# Arduino_MEGA2560_ref.net
KiCad netlist of a schematic drawn in EAGLE
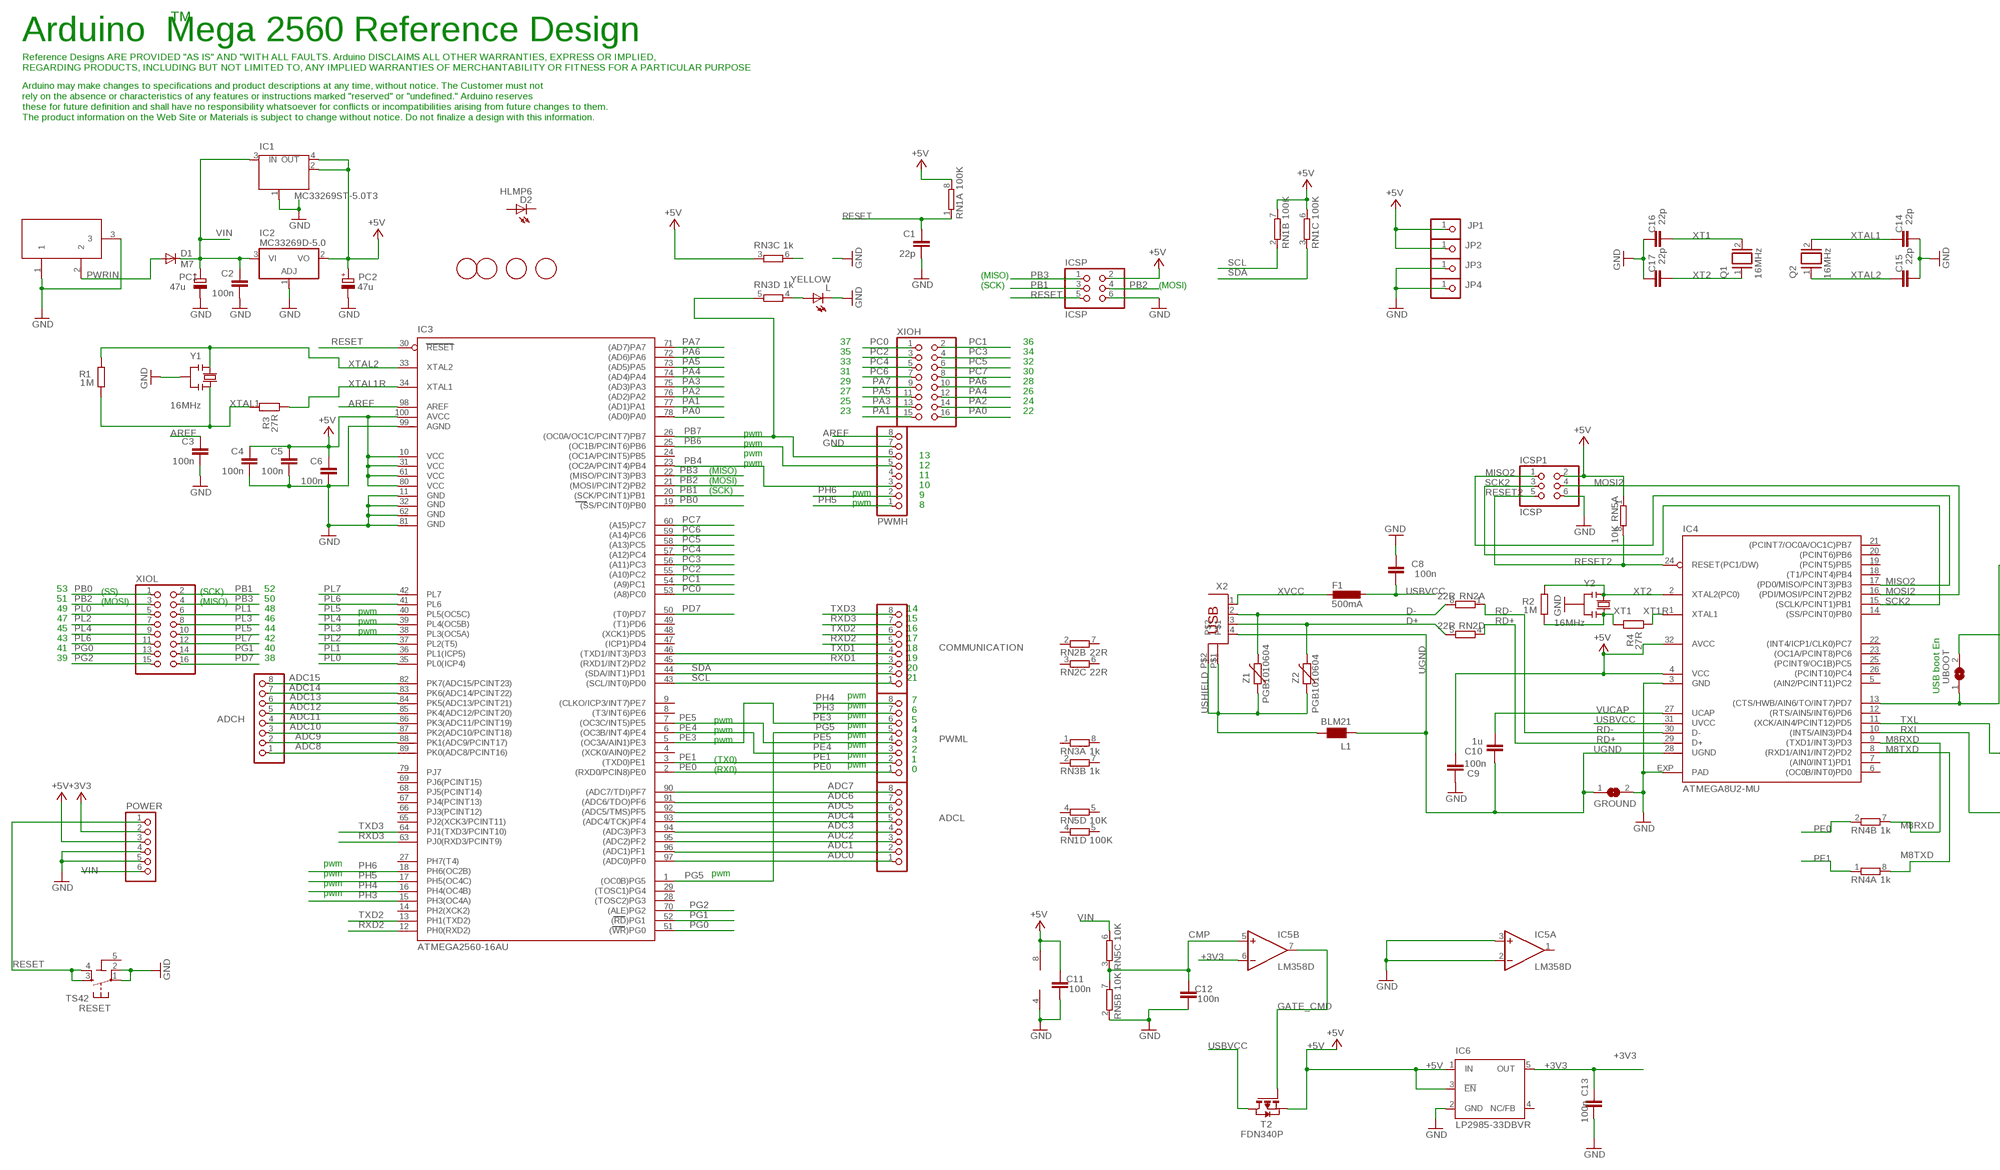
[diagram p0: schematic, sheet 1, part 1 of 2]
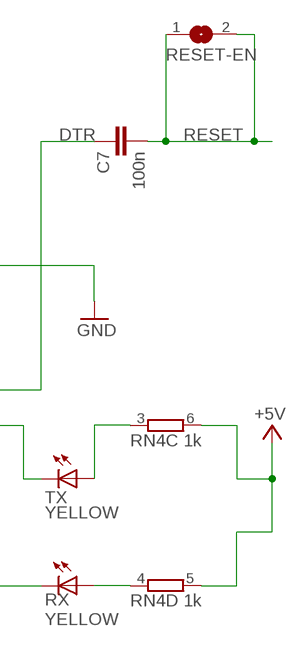
[diagram p1: schematic, sheet 1, part 2 of 2]

(export (version "E")
  (design (tool "Eeschema 10.0.6"))
  (components
    (comp (ref "ADCH")
      (value "PINHD-1X8")
      (footprint "eagle-import:1X08")
      (libsource (lib "eagle-import") (part "PINHD-1X8"))
    )
    (comp (ref "ADCL")
      (value "PINHD-1X8")
      (footprint "eagle-import:1X08")
      (libsource (lib "eagle-import") (part "PINHD-1X8"))
    )
    (comp (ref "C1")
      (value "22p")
      (footprint "eagle-import:C0603-ROUND")
      (libsource (lib "eagle-import") (part "C-EU0603-RND"))
    )
    (comp (ref "C2")
      (value "100n")
      (footprint "eagle-import:C0603-ROUND")
      (libsource (lib "eagle-import") (part "C-EU0603-RND"))
    )
    (comp (ref "C3")
      (value "100n")
      (footprint "eagle-import:C0603-ROUND")
      (libsource (lib "eagle-import") (part "C-EU0603-RND"))
    )
    (comp (ref "C4")
      (value "100n")
      (footprint "eagle-import:C0603-ROUND")
      (libsource (lib "eagle-import") (part "C-EU0603-RND"))
    )
    (comp (ref "C5")
      (value "100n")
      (footprint "eagle-import:C0603-ROUND")
      (libsource (lib "eagle-import") (part "C-EU0603-RND"))
    )
    (comp (ref "C6")
      (value "100n")
      (footprint "eagle-import:C0603-ROUND")
      (libsource (lib "eagle-import") (part "C-EU0603-RND"))
    )
    (comp (ref "C7")
      (value "100n")
      (footprint "eagle-import:C0603-ROUND")
      (libsource (lib "eagle-import") (part "C-EU0603-RND"))
    )
    (comp (ref "C8")
      (value "100n")
      (footprint "eagle-import:C0603")
      (libsource (lib "eagle-import") (part "rcl_C-EUC0603"))
    )
    (comp (ref "C9")
      (value "100n")
      (footprint "eagle-import:C0603-ROUND")
      (libsource (lib "eagle-import") (part "C-EU0603-RND"))
    )
    (comp (ref "C10")
      (value "1u")
      (footprint "eagle-import:C0603-ROUND")
      (libsource (lib "eagle-import") (part "C-EU0603-RND"))
    )
    (comp (ref "C11")
      (value "100n")
      (footprint "eagle-import:C0603")
      (libsource (lib "eagle-import") (part "rcl_C-EUC0603"))
    )
    (comp (ref "C12")
      (value "100n")
      (footprint "eagle-import:C0603-ROUND")
      (libsource (lib "eagle-import") (part "C-EU0603-RND"))
    )
    (comp (ref "C13")
      (value "100n")
      (footprint "eagle-import:C0603-ROUND")
      (libsource (lib "eagle-import") (part "C-EU0603-RND"))
    )
    (comp (ref "C14")
      (value "22p")
      (footprint "eagle-import:C0603-ROUND")
      (libsource (lib "eagle-import") (part "C-EU0603-RND"))
    )
    (comp (ref "C15")
      (value "22p")
      (footprint "eagle-import:C0603-ROUND")
      (libsource (lib "eagle-import") (part "C-EU0603-RND"))
    )
    (comp (ref "C16")
      (value "22p")
      (footprint "eagle-import:C0603-ROUND")
      (libsource (lib "eagle-import") (part "C-EU0603-RND"))
    )
    (comp (ref "C17")
      (value "22p")
      (footprint "eagle-import:C0603-ROUND")
      (libsource (lib "eagle-import") (part "C-EU0603-RND"))
    )
    (comp (ref "COMMUNICATION")
      (value "PINHD-1X8")
      (footprint "eagle-import:1X08")
      (libsource (lib "eagle-import") (part "PINHD-1X8"))
    )
    (comp (ref "D1")
      (value "M7")
      (footprint "eagle-import:SMB")
      (libsource (lib "eagle-import") (part "DIODE-SMB"))
    )
    (comp (ref "D2")
      (value "HLMP6")
      (footprint "eagle-import:HLMP6")
      (fields (field (name "MF") "AGILENT TECHNOLOGIES") (field (name "MPN") "HLMP-6500"))
      (libsource (lib "eagle-import") (part "HLMP6"))
    )
    (comp (ref "F1")
      (value "500mA")
      (footprint "eagle-import:L1812")
      (libsource (lib "eagle-import") (part "L-EUL1812"))
    )
    (comp (ref "GROUND")
      (value "SJ")
      (footprint "eagle-import:SJ")
      (libsource (lib "eagle-import") (part "SJ"))
    )
    (comp (ref "IC1")
      (value "MC33269ST-5.0T3")
      (footprint "eagle-import:SOT223")
      (libsource (lib "eagle-import") (part "MC33269ST-3.3T3"))
    )
    (comp (ref "IC2")
      (value "MC33269D-5.0")
      (footprint "eagle-import:DPACK")
      (libsource (lib "eagle-import") (part "MC33269?D-5.0"))
    )
    (comp (ref "IC3")
      (value "ATMEGA2560-16AU")
      (footprint "eagle-import:TQFP100")
      (libsource (lib "eagle-import") (part "ATMEGAAU1280-16"))
    )
    (comp (ref "IC4")
      (value "ATMEGA8U2-MU")
      (footprint "eagle-import:QFN32")
      (libsource (lib "eagle-import") (part "ATMEGA8U2-MU"))
    )
    (comp (ref "IC5")
      (value "LM358D")
      (footprint "eagle-import:SO08")
      (libsource (lib "eagle-import") (part "LM358D"))
    )
    (comp (ref "IC6")
      (value "LP2985-33DBVR")
      (footprint "eagle-import:SOT23-DBV")
      (libsource (lib "eagle-import") (part "TPS77033"))
    )
    (comp (ref "ICSP")
      (value "ICSP")
      (footprint "eagle-import:2X03")
      (libsource (lib "eagle-import") (part "PINHD-2X3"))
    )
    (comp (ref "ICSP1")
      (value "ICSP")
      (footprint "eagle-import:2X03")
      (libsource (lib "eagle-import") (part "PINHD-2X3"))
    )
    (comp (ref "JP1")
      (value "PINHD-1X1")
      (footprint "eagle-import:1X01")
      (libsource (lib "eagle-import") (part "PINHD-1X1"))
    )
    (comp (ref "JP2")
      (value "PINHD-1X1")
      (footprint "eagle-import:1X01")
      (libsource (lib "eagle-import") (part "PINHD-1X1"))
    )
    (comp (ref "JP3")
      (value "PINHD-1X1")
      (footprint "eagle-import:1X01")
      (libsource (lib "eagle-import") (part "PINHD-1X1"))
    )
    (comp (ref "JP4")
      (value "PINHD-1X1")
      (footprint "eagle-import:1X01")
      (libsource (lib "eagle-import") (part "PINHD-1X1"))
    )
    (comp (ref "L")
      (value "YELLOW")
      (footprint "eagle-import:CHIP-LED0805")
      (libsource (lib "eagle-import") (part "LEDCHIP-LED0805"))
    )
    (comp (ref "L1")
      (value "BLM21")
      (footprint "eagle-import:0805")
      (libsource (lib "eagle-import") (part "WE-CBF_0805"))
    )
    (comp (ref "PC1")
      (value "47u")
      (footprint "eagle-import:PANASONIC_D")
      (libsource (lib "eagle-import") (part "CPOL-EUD"))
    )
    (comp (ref "PC2")
      (value "47u")
      (footprint "eagle-import:PANASONIC_D")
      (libsource (lib "eagle-import") (part "CPOL-EUD"))
    )
    (comp (ref "POWER")
      (value "PINHD-1X6")
      (footprint "eagle-import:1X06")
      (libsource (lib "eagle-import") (part "PINHD-1X6"))
    )
    (comp (ref "PWMH")
      (value "PINHD-1X8")
      (footprint "eagle-import:1X08")
      (libsource (lib "eagle-import") (part "PINHD-1X8"))
    )
    (comp (ref "PWML")
      (value "PINHD-1X8")
      (footprint "eagle-import:1X08")
      (libsource (lib "eagle-import") (part "PINHD-1X8"))
    )
    (comp (ref "Q1")
      (value "16MHz")
      (footprint "eagle-import:QS")
      (libsource (lib "eagle-import") (part "XTAL/S"))
    )
    (comp (ref "Q2")
      (value "16MHz")
      (footprint "eagle-import:QS")
      (libsource (lib "eagle-import") (part "XTAL/S"))
    )
    (comp (ref "R1")
      (value "1M")
      (footprint "eagle-import:R0603-ROUND")
      (libsource (lib "eagle-import") (part "R-EU_R0603"))
    )
    (comp (ref "R2")
      (value "1M")
      (footprint "eagle-import:R0603-ROUND")
      (libsource (lib "eagle-import") (part "R-EU_R0603"))
    )
    (comp (ref "R3")
      (value "27R")
      (footprint "eagle-import:R0603-ROUND")
      (libsource (lib "eagle-import") (part "R-EU_R0603"))
    )
    (comp (ref "R4")
      (value "27R")
      (footprint "eagle-import:R0603-ROUND")
      (libsource (lib "eagle-import") (part "R-EU_R0603"))
    )
    (comp (ref "RESET")
      (value "TS42")
      (footprint "eagle-import:TS42")
      (libsource (lib "eagle-import") (part "TS42"))
    )
    (comp (ref "RESET-EN")
      (value "SJ")
      (footprint "eagle-import:SJ")
      (libsource (lib "eagle-import") (part "SJ"))
    )
    (comp (ref "RN1")
      (value "100K")
      (footprint "eagle-import:CAT16")
      (libsource (lib "eagle-import") (part "4R-NCAT16"))
    )
    (comp (ref "RN2")
      (value "22R")
      (footprint "eagle-import:CAY16")
      (libsource (lib "eagle-import") (part "4R-NCAY16"))
    )
    (comp (ref "RN3")
      (value "1k")
      (footprint "eagle-import:CAY16")
      (libsource (lib "eagle-import") (part "4R-NCAY16"))
    )
    (comp (ref "RN4")
      (value "1k")
      (footprint "eagle-import:CAY16")
      (libsource (lib "eagle-import") (part "4R-NCAY16"))
    )
    (comp (ref "RN5")
      (value "10K")
      (footprint "eagle-import:CAT16")
      (libsource (lib "eagle-import") (part "4R-NCAT16"))
    )
    (comp (ref "RX")
      (value "YELLOW")
      (footprint "eagle-import:CHIP-LED0805")
      (libsource (lib "eagle-import") (part "LEDCHIP-LED0805"))
    )
    (comp (ref "T2")
      (value "FDN340P")
      (footprint "eagle-import:SOT-23")
      (libsource (lib "eagle-import") (part "PMOSSOT23"))
    )
    (comp (ref "TX")
      (value "YELLOW")
      (footprint "eagle-import:CHIP-LED0805")
      (libsource (lib "eagle-import") (part "LEDCHIP-LED0805"))
    )
    (comp (ref "U$2")
      (value "FIDUCIALMOUNT")
      (footprint "eagle-import:FIDUCIA-MOUNT")
      (libsource (lib "eagle-import") (part "FIDUCIALMOUNT"))
    )
    (comp (ref "U$3")
      (value "FIDUCIALMOUNT")
      (footprint "eagle-import:FIDUCIA-MOUNT")
      (libsource (lib "eagle-import") (part "FIDUCIALMOUNT"))
    )
    (comp (ref "U$4")
      (value "FIDUCIALMOUNT")
      (footprint "eagle-import:FIDUCIA-MOUNT")
      (libsource (lib "eagle-import") (part "FIDUCIALMOUNT"))
    )
    (comp (ref "U$5")
      (value "FIDUCIALMOUNT")
      (footprint "eagle-import:FIDUCIA-MOUNT")
      (libsource (lib "eagle-import") (part "FIDUCIALMOUNT"))
    )
    (comp (ref "UBOOT")
      (value "SJ")
      (footprint "eagle-import:SJ")
      (libsource (lib "eagle-import") (part "SJ"))
    )
    (comp (ref "X1")
      (value "DC21MMX")
      (footprint "eagle-import:DC-21MM")
      (libsource (lib "eagle-import") (part "DC21MMX"))
    )
    (comp (ref "X2")
      (value "PN61729")
      (footprint "eagle-import:PN61729")
      (libsource (lib "eagle-import") (part "PN61729"))
    )
    (comp (ref "XIOH")
      (value "PINHD-2X8")
      (footprint "eagle-import:2X08")
      (libsource (lib "eagle-import") (part "PINHD-2X8"))
    )
    (comp (ref "XIOL")
      (value "PINHD-2X8")
      (footprint "eagle-import:2X08")
      (libsource (lib "eagle-import") (part "PINHD-2X8"))
    )
    (comp (ref "Y1")
      (value "16MHz")
      (footprint "eagle-import:RESONATOR")
      (libsource (lib "eagle-import") (part "RESONATORMU"))
    )
    (comp (ref "Y2")
      (value "16MHz")
      (footprint "eagle-import:RESONATOR")
      (libsource (lib "eagle-import") (part "RESONATORMU"))
    )
    (comp (ref "Z1")
      (value "PGB1010604")
      (footprint "eagle-import:CT_CN0603")
      (libsource (lib "eagle-import") (part "VARISTORCN0603"))
    )
    (comp (ref "Z2")
      (value "PGB1010604")
      (footprint "eagle-import:CT_CN0603")
      (libsource (lib "eagle-import") (part "VARISTORCN0603"))
    )
  )
  (nets
    (net (code "1") (name "+3V3") (class "Default")
      (node (ref "C13") (pin "2") (pinfunction "2_2") (pintype "passive"))
      (node (ref "IC5") (pin "6") (pinfunction "-IN_6") (pintype "input"))
      (node (ref "IC6") (pin "5") (pinfunction "OUT_5") (pintype "passive"))
      (node (ref "POWER") (pin "2") (pinfunction "2_2") (pintype "passive"))
    )
    (net (code "2") (name "+5V") (class "Default")
      (node (ref "C11") (pin "2") (pinfunction "2_2") (pintype "passive"))
      (node (ref "C4") (pin "1") (pinfunction "1_1") (pintype "passive"))
      (node (ref "C5") (pin "1") (pinfunction "1_1") (pintype "passive"))
      (node (ref "C6") (pin "1") (pinfunction "1_1") (pintype "passive"))
      (node (ref "C9") (pin "1") (pinfunction "1_1") (pintype "passive"))
      (node (ref "IC1") (pin "2") (pinfunction "OUT_2") (pintype "passive"))
      (node (ref "IC1") (pin "4") (pinfunction "OUT_4") (pintype "passive"))
      (node (ref "IC2") (pin "2") (pinfunction "VO_2") (pintype "passive"))
      (node (ref "IC3") (pin "10") (pinfunction "VCC_10") (pintype "power_in"))
      (node (ref "IC3") (pin "100") (pinfunction "AVCC_100") (pintype "power_in"))
      (node (ref "IC3") (pin "31") (pinfunction "VCC1_31") (pintype "power_in"))
      (node (ref "IC3") (pin "61") (pinfunction "VCC2_61") (pintype "power_in"))
      (node (ref "IC3") (pin "80") (pinfunction "VCC3_80") (pintype "power_in"))
      (node (ref "IC4") (pin "32") (pinfunction "AVCC_32") (pintype "power_in"))
      (node (ref "IC4") (pin "4") (pinfunction "VCC_4") (pintype "power_in"))
      (node (ref "IC5") (pin "8") (pinfunction "V+_8") (pintype "power_in"))
      (node (ref "IC6") (pin "1") (pinfunction "IN_1") (pintype "input"))
      (node (ref "IC6") (pin "3") (pinfunction "~{EN}_3") (pintype "input"))
      (node (ref "ICSP") (pin "2") (pinfunction "2_2") (pintype "passive"))
      (node (ref "ICSP1") (pin "2") (pinfunction "2_2") (pintype "passive"))
      (node (ref "JP1") (pin "1") (pinfunction "1_1") (pintype "passive"))
      (node (ref "JP2") (pin "1") (pinfunction "1_1") (pintype "passive"))
      (node (ref "PC2") (pin "+") (pinfunction "+_+") (pintype "passive"))
      (node (ref "POWER") (pin "3") (pinfunction "3_3") (pintype "passive"))
      (node (ref "RN1") (pin "6") (pinfunction "2_6") (pintype "passive"))
      (node (ref "RN1") (pin "7") (pinfunction "2_7") (pintype "passive"))
      (node (ref "RN1") (pin "8") (pinfunction "2_8") (pintype "passive"))
      (node (ref "RN3") (pin "3") (pinfunction "1_3") (pintype "passive"))
      (node (ref "RN4") (pin "5") (pinfunction "2_5") (pintype "passive"))
      (node (ref "RN4") (pin "6") (pinfunction "2_6") (pintype "passive"))
      (node (ref "RN5") (pin "1") (pinfunction "1_1") (pintype "passive"))
      (node (ref "T2") (pin "2") (pinfunction "S_2") (pintype "passive"))
    )
    (net (code "3") (name "/5-GND") (class "Default")
      (node (ref "RESET") (pin "5") (pinfunction "5-GND_5") (pintype "power_in"))
    )
    (net (code "4") (name "/ADC0") (class "Default")
      (node (ref "ADCL") (pin "1") (pinfunction "1_1") (pintype "passive"))
      (node (ref "IC3") (pin "97") (pinfunction "(ADC0)PF0_97") (pintype "bidirectional"))
    )
    (net (code "5") (name "/ADC1") (class "Default")
      (node (ref "ADCL") (pin "2") (pinfunction "2_2") (pintype "passive"))
      (node (ref "IC3") (pin "96") (pinfunction "(ADC1)PF1_96") (pintype "bidirectional"))
    )
    (net (code "6") (name "/ADC2") (class "Default")
      (node (ref "ADCL") (pin "3") (pinfunction "3_3") (pintype "passive"))
      (node (ref "IC3") (pin "95") (pinfunction "(ADC2)PF2_95") (pintype "bidirectional"))
    )
    (net (code "7") (name "/ADC3") (class "Default")
      (node (ref "ADCL") (pin "4") (pinfunction "4_4") (pintype "passive"))
      (node (ref "IC3") (pin "94") (pinfunction "(ADC3)PF3_94") (pintype "bidirectional"))
    )
    (net (code "8") (name "/ADC4") (class "Default")
      (node (ref "ADCL") (pin "5") (pinfunction "5_5") (pintype "passive"))
      (node (ref "IC3") (pin "93") (pinfunction "(ADC4/TCK)PF4_93") (pintype "bidirectional"))
    )
    (net (code "9") (name "/ADC5") (class "Default")
      (node (ref "ADCL") (pin "6") (pinfunction "6_6") (pintype "passive"))
      (node (ref "IC3") (pin "92") (pinfunction "(ADC5/TMS)PF5_92") (pintype "bidirectional"))
    )
    (net (code "10") (name "/ADC6") (class "Default")
      (node (ref "ADCL") (pin "7") (pinfunction "7_7") (pintype "passive"))
      (node (ref "IC3") (pin "91") (pinfunction "(ADC6/TDO)PF6_91") (pintype "bidirectional"))
    )
    (net (code "11") (name "/ADC7") (class "Default")
      (node (ref "ADCL") (pin "8") (pinfunction "8_8") (pintype "passive"))
      (node (ref "IC3") (pin "90") (pinfunction "(ADC7/TDI)PF7_90") (pintype "bidirectional"))
    )
    (net (code "12") (name "/ADC8") (class "Default")
      (node (ref "ADCH") (pin "1") (pinfunction "1_1") (pintype "passive"))
      (node (ref "IC3") (pin "89") (pinfunction "PK0(ADC8/PCINT16)_89") (pintype "bidirectional"))
    )
    (net (code "13") (name "/ADC9") (class "Default")
      (node (ref "ADCH") (pin "2") (pinfunction "2_2") (pintype "passive"))
      (node (ref "IC3") (pin "88") (pinfunction "PK1(ADC9/PCINT17)_88") (pintype "bidirectional"))
    )
    (net (code "14") (name "/ADC10") (class "Default")
      (node (ref "ADCH") (pin "3") (pinfunction "3_3") (pintype "passive"))
      (node (ref "IC3") (pin "87") (pinfunction "PK2(ADC10/PCINT18)_87") (pintype "bidirectional"))
    )
    (net (code "15") (name "/ADC11") (class "Default")
      (node (ref "ADCH") (pin "4") (pinfunction "4_4") (pintype "passive"))
      (node (ref "IC3") (pin "86") (pinfunction "PK3(ADC11/PCINT19)_86") (pintype "bidirectional"))
    )
    (net (code "16") (name "/ADC12") (class "Default")
      (node (ref "ADCH") (pin "5") (pinfunction "5_5") (pintype "passive"))
      (node (ref "IC3") (pin "85") (pinfunction "PK4(ADC12/PCINT20)_85") (pintype "bidirectional"))
    )
    (net (code "17") (name "/ADC13") (class "Default")
      (node (ref "ADCH") (pin "6") (pinfunction "6_6") (pintype "passive"))
      (node (ref "IC3") (pin "84") (pinfunction "PK5(ADC13/PCINT21)_84") (pintype "bidirectional"))
    )
    (net (code "18") (name "/ADC14") (class "Default")
      (node (ref "ADCH") (pin "7") (pinfunction "7_7") (pintype "passive"))
      (node (ref "IC3") (pin "83") (pinfunction "PK6(ADC14/PCINT22)_83") (pintype "bidirectional"))
    )
    (net (code "19") (name "/ADC15") (class "Default")
      (node (ref "ADCH") (pin "8") (pinfunction "8_8") (pintype "passive"))
      (node (ref "IC3") (pin "82") (pinfunction "PK7(ADC15/PCINT23)_82") (pintype "bidirectional"))
    )
    (net (code "20") (name "/AREF") (class "Default")
      (node (ref "C3") (pin "1") (pinfunction "1_1") (pintype "passive"))
      (node (ref "IC3") (pin "98") (pinfunction "AREF_98") (pintype "bidirectional"))
      (node (ref "PWMH") (pin "8") (pinfunction "8_8") (pintype "passive"))
    )
    (net (code "21") (name "/CMP") (class "Default")
      (node (ref "C12") (pin "2") (pinfunction "2_2") (pintype "passive"))
      (node (ref "IC5") (pin "5") (pinfunction "+IN_5") (pintype "input"))
      (node (ref "RN5") (pin "3") (pinfunction "1_3") (pintype "passive"))
      (node (ref "RN5") (pin "7") (pinfunction "2_7") (pintype "passive"))
    )
    (net (code "22") (name "/D+") (class "Default")
      (node (ref "RN2") (pin "5") (pinfunction "2_5") (pintype "passive"))
      (node (ref "X2") (pin "3") (pinfunction "3_3") (pintype "bidirectional"))
      (node (ref "Z2") (pin "2") (pinfunction "2_2") (pintype "passive"))
    )
    (net (code "23") (name "/D-") (class "Default")
      (node (ref "RN2") (pin "8") (pinfunction "2_8") (pintype "passive"))
      (node (ref "X2") (pin "2") (pinfunction "2_2") (pintype "bidirectional"))
      (node (ref "Z1") (pin "2") (pinfunction "2_2") (pintype "passive"))
    )
    (net (code "24") (name "/DTR") (class "Default")
      (node (ref "C7") (pin "1") (pinfunction "1_1") (pintype "passive"))
      (node (ref "IC4") (pin "13") (pinfunction "(CTS/HWB/AIN6/TO/INT7)PD7_13") (pintype "bidirectional"))
      (node (ref "UBOOT") (pin "1") (pinfunction "1_1") (pintype "passive"))
    )
    (net (code "25") (name "/GATE_CMD") (class "Default")
      (node (ref "IC5") (pin "7") (pinfunction "OUT_7") (pintype "output"))
      (node (ref "T2") (pin "3") (pinfunction "G_3") (pintype "passive"))
    )
    (net (code "26") (name "/M8RXD") (class "Default")
      (node (ref "IC4") (pin "9") (pinfunction "(TXD1/INT3)PD3_9") (pintype "bidirectional"))
      (node (ref "RN4") (pin "7") (pinfunction "2_7") (pintype "passive"))
    )
    (net (code "27") (name "/M8TXD") (class "Default")
      (node (ref "IC4") (pin "8") (pinfunction "(RXD1/AIN1/INT2)PD2_8") (pintype "bidirectional"))
      (node (ref "RN4") (pin "8") (pinfunction "2_8") (pintype "passive"))
    )
    (net (code "28") (name "/MISO2") (class "Default")
      (node (ref "IC4") (pin "17") (pinfunction "(PD0/MISO/PCINT3)PB3_17") (pintype "bidirectional"))
      (node (ref "ICSP1") (pin "1") (pinfunction "1_1") (pintype "passive"))
    )
    (net (code "29") (name "/MOSI2") (class "Default")
      (node (ref "IC4") (pin "16") (pinfunction "(PDI/MOSI/PCINT2)PB2_16") (pintype "bidirectional"))
      (node (ref "ICSP1") (pin "4") (pinfunction "4_4") (pintype "passive"))
    )
    (net (code "30") (name "/PA0") (class "Default")
      (node (ref "IC3") (pin "78") (pinfunction "(AD0)PA0_78") (pintype "bidirectional"))
      (node (ref "XIOH") (pin "16") (pinfunction "16_16") (pintype "passive"))
    )
    (net (code "31") (name "/PA1") (class "Default")
      (node (ref "IC3") (pin "77") (pinfunction "(AD1)PA1_77") (pintype "bidirectional"))
      (node (ref "XIOH") (pin "15") (pinfunction "15_15") (pintype "passive"))
    )
    (net (code "32") (name "/PA2") (class "Default")
      (node (ref "IC3") (pin "76") (pinfunction "(AD2)PA2_76") (pintype "bidirectional"))
      (node (ref "XIOH") (pin "14") (pinfunction "14_14") (pintype "passive"))
    )
    (net (code "33") (name "/PA3") (class "Default")
      (node (ref "IC3") (pin "75") (pinfunction "(AD3)PA3_75") (pintype "bidirectional"))
      (node (ref "XIOH") (pin "13") (pinfunction "13_13") (pintype "passive"))
    )
    (net (code "34") (name "/PA4") (class "Default")
      (node (ref "IC3") (pin "74") (pinfunction "(AD4)PA4_74") (pintype "bidirectional"))
      (node (ref "XIOH") (pin "12") (pinfunction "12_12") (pintype "passive"))
    )
    (net (code "35") (name "/PA5") (class "Default")
      (node (ref "IC3") (pin "73") (pinfunction "(AD5)PA5_73") (pintype "bidirectional"))
      (node (ref "XIOH") (pin "11") (pinfunction "11_11") (pintype "passive"))
    )
    (net (code "36") (name "/PA6") (class "Default")
      (node (ref "IC3") (pin "72") (pinfunction "(AD6)PA6_72") (pintype "bidirectional"))
      (node (ref "XIOH") (pin "10") (pinfunction "10_10") (pintype "passive"))
    )
    (net (code "37") (name "/PA7") (class "Default")
      (node (ref "IC3") (pin "71") (pinfunction "(AD7)PA7_71") (pintype "bidirectional"))
      (node (ref "XIOH") (pin "9") (pinfunction "9_9") (pintype "passive"))
    )
    (net (code "38") (name "/PB0") (class "Default")
      (node (ref "IC3") (pin "19") (pinfunction "(SS/PCINT0)PB0_19") (pintype "bidirectional"))
      (node (ref "XIOL") (pin "1") (pinfunction "1_1") (pintype "passive"))
    )
    (net (code "39") (name "/PB1") (class "Default")
      (node (ref "IC3") (pin "20") (pinfunction "(SCK/PCINT1)PB1_20") (pintype "bidirectional"))
      (node (ref "ICSP") (pin "3") (pinfunction "3_3") (pintype "passive"))
      (node (ref "XIOL") (pin "2") (pinfunction "2_2") (pintype "passive"))
    )
    (net (code "40") (name "/PB2") (class "Default")
      (node (ref "IC3") (pin "21") (pinfunction "(MOSI/PCINT2)PB2_21") (pintype "bidirectional"))
      (node (ref "ICSP") (pin "4") (pinfunction "4_4") (pintype "passive"))
      (node (ref "XIOL") (pin "3") (pinfunction "3_3") (pintype "passive"))
    )
    (net (code "41") (name "/PB3") (class "Default")
      (node (ref "IC3") (pin "22") (pinfunction "(MISO/PCINT3)PB3_22") (pintype "bidirectional"))
      (node (ref "ICSP") (pin "1") (pinfunction "1_1") (pintype "passive"))
      (node (ref "XIOL") (pin "4") (pinfunction "4_4") (pintype "passive"))
    )
    (net (code "42") (name "/PB4") (class "Default")
      (node (ref "IC3") (pin "23") (pinfunction "(OC2A/PCINT4)PB4_23") (pintype "bidirectional"))
      (node (ref "PWMH") (pin "3") (pinfunction "3_3") (pintype "passive"))
    )
    (net (code "43") (name "/PB6") (class "Default")
      (node (ref "IC3") (pin "25") (pinfunction "(OC1B/PCINT6)PB6_25") (pintype "bidirectional"))
      (node (ref "PWMH") (pin "5") (pinfunction "5_5") (pintype "passive"))
    )
    (net (code "44") (name "/PB7") (class "Default")
      (node (ref "IC3") (pin "26") (pinfunction "(OC0A/OC1C/PCINT7)PB7_26") (pintype "bidirectional"))
      (node (ref "PWMH") (pin "6") (pinfunction "6_6") (pintype "passive"))
      (node (ref "RN3") (pin "5") (pinfunction "2_5") (pintype "passive"))
    )
    (net (code "45") (name "/PC0") (class "Default")
      (node (ref "IC3") (pin "53") (pinfunction "(A8)PC0_53") (pintype "bidirectional"))
      (node (ref "XIOH") (pin "1") (pinfunction "1_1") (pintype "passive"))
    )
    (net (code "46") (name "/PC1") (class "Default")
      (node (ref "IC3") (pin "54") (pinfunction "(A9)PC1_54") (pintype "bidirectional"))
      (node (ref "XIOH") (pin "2") (pinfunction "2_2") (pintype "passive"))
    )
    (net (code "47") (name "/PC2") (class "Default")
      (node (ref "IC3") (pin "55") (pinfunction "(A10)PC2_55") (pintype "bidirectional"))
      (node (ref "XIOH") (pin "3") (pinfunction "3_3") (pintype "passive"))
    )
    (net (code "48") (name "/PC3") (class "Default")
      (node (ref "IC3") (pin "56") (pinfunction "(A11)PC3_56") (pintype "bidirectional"))
      (node (ref "XIOH") (pin "4") (pinfunction "4_4") (pintype "passive"))
    )
    (net (code "49") (name "/PC4") (class "Default")
      (node (ref "IC3") (pin "57") (pinfunction "(A12)PC4_57") (pintype "bidirectional"))
      (node (ref "XIOH") (pin "5") (pinfunction "5_5") (pintype "passive"))
    )
    (net (code "50") (name "/PC5") (class "Default")
      (node (ref "IC3") (pin "58") (pinfunction "(A13)PC5_58") (pintype "bidirectional"))
      (node (ref "XIOH") (pin "6") (pinfunction "6_6") (pintype "passive"))
    )
    (net (code "51") (name "/PC6") (class "Default")
      (node (ref "IC3") (pin "59") (pinfunction "(A14)PC6_59") (pintype "bidirectional"))
      (node (ref "XIOH") (pin "7") (pinfunction "7_7") (pintype "passive"))
    )
    (net (code "52") (name "/PC7") (class "Default")
      (node (ref "IC3") (pin "60") (pinfunction "(A15)PC7_60") (pintype "bidirectional"))
      (node (ref "XIOH") (pin "8") (pinfunction "8_8") (pintype "passive"))
    )
    (net (code "53") (name "/PD7") (class "Default")
      (node (ref "IC3") (pin "50") (pinfunction "(T0)PD7_50") (pintype "bidirectional"))
      (node (ref "XIOL") (pin "16") (pinfunction "16_16") (pintype "passive"))
    )
    (net (code "54") (name "/PE0") (class "Default")
      (node (ref "IC3") (pin "2") (pinfunction "(RXD0/PCIN8)PE0_2") (pintype "bidirectional"))
      (node (ref "PWML") (pin "1") (pinfunction "1_1") (pintype "passive"))
      (node (ref "RN4") (pin "2") (pinfunction "1_2") (pintype "passive"))
    )
    (net (code "55") (name "/PE1") (class "Default")
      (node (ref "IC3") (pin "3") (pinfunction "(TXD0)PE1_3") (pintype "bidirectional"))
      (node (ref "PWML") (pin "2") (pinfunction "2_2") (pintype "passive"))
      (node (ref "RN4") (pin "1") (pinfunction "1_1") (pintype "passive"))
    )
    (net (code "56") (name "/PE3") (class "Default")
      (node (ref "IC3") (pin "5") (pinfunction "(OC3A/AIN1)PE3_5") (pintype "bidirectional"))
      (node (ref "PWML") (pin "6") (pinfunction "6_6") (pintype "passive"))
    )
    (net (code "57") (name "/PE4") (class "Default")
      (node (ref "IC3") (pin "6") (pinfunction "(OC3B/INT4)PE4_6") (pintype "bidirectional"))
      (node (ref "PWML") (pin "3") (pinfunction "3_3") (pintype "passive"))
    )
    (net (code "58") (name "/PE5") (class "Default")
      (node (ref "IC3") (pin "7") (pinfunction "(OC3C/INT5)PE5_7") (pintype "bidirectional"))
      (node (ref "PWML") (pin "4") (pinfunction "4_4") (pintype "passive"))
    )
    (net (code "59") (name "/PG0") (class "Default")
      (node (ref "IC3") (pin "51") (pinfunction "(WR)PG0_51") (pintype "bidirectional"))
      (node (ref "XIOL") (pin "13") (pinfunction "13_13") (pintype "passive"))
    )
    (net (code "60") (name "/PG1") (class "Default")
      (node (ref "IC3") (pin "52") (pinfunction "(RD)PG1_52") (pintype "bidirectional"))
      (node (ref "XIOL") (pin "14") (pinfunction "14_14") (pintype "passive"))
    )
    (net (code "61") (name "/PG2") (class "Default")
      (node (ref "IC3") (pin "70") (pinfunction "(ALE)PG2_70") (pintype "bidirectional"))
      (node (ref "XIOL") (pin "15") (pinfunction "15_15") (pintype "passive"))
    )
    (net (code "62") (name "/PG5") (class "Default")
      (node (ref "IC3") (pin "1") (pinfunction "(OC0B)PG5_1") (pintype "bidirectional"))
      (node (ref "PWML") (pin "5") (pinfunction "5_5") (pintype "passive"))
    )
    (net (code "63") (name "/PH3") (class "Default")
      (node (ref "IC3") (pin "15") (pinfunction "PH3(OC4A)_15") (pintype "bidirectional"))
      (node (ref "PWML") (pin "7") (pinfunction "7_7") (pintype "passive"))
    )
    (net (code "64") (name "/PH4") (class "Default")
      (node (ref "IC3") (pin "16") (pinfunction "PH4(OC4B)_16") (pintype "bidirectional"))
      (node (ref "PWML") (pin "8") (pinfunction "8_8") (pintype "passive"))
    )
    (net (code "65") (name "/PH5") (class "Default")
      (node (ref "IC3") (pin "17") (pinfunction "PH5(OC4C)_17") (pintype "bidirectional"))
      (node (ref "PWMH") (pin "1") (pinfunction "1_1") (pintype "passive"))
    )
    (net (code "66") (name "/PH6") (class "Default")
      (node (ref "IC3") (pin "18") (pinfunction "PH6(OC2B)_18") (pintype "bidirectional"))
      (node (ref "PWMH") (pin "2") (pinfunction "2_2") (pintype "passive"))
    )
    (net (code "67") (name "/PL0") (class "Default")
      (node (ref "IC3") (pin "35") (pinfunction "PL0(ICP4)_35") (pintype "bidirectional"))
      (node (ref "XIOL") (pin "5") (pinfunction "5_5") (pintype "passive"))
    )
    (net (code "68") (name "/PL1") (class "Default")
      (node (ref "IC3") (pin "36") (pinfunction "PL1(ICP5)_36") (pintype "bidirectional"))
      (node (ref "XIOL") (pin "6") (pinfunction "6_6") (pintype "passive"))
    )
    (net (code "69") (name "/PL2") (class "Default")
      (node (ref "IC3") (pin "37") (pinfunction "PL2(T5)_37") (pintype "bidirectional"))
      (node (ref "XIOL") (pin "7") (pinfunction "7_7") (pintype "passive"))
    )
    (net (code "70") (name "/PL3") (class "Default")
      (node (ref "IC3") (pin "38") (pinfunction "PL3(OC5A)_38") (pintype "bidirectional"))
      (node (ref "XIOL") (pin "8") (pinfunction "8_8") (pintype "passive"))
    )
    (net (code "71") (name "/PL4") (class "Default")
      (node (ref "IC3") (pin "39") (pinfunction "PL4(OC5B)_39") (pintype "bidirectional"))
      (node (ref "XIOL") (pin "9") (pinfunction "9_9") (pintype "passive"))
    )
    (net (code "72") (name "/PL5") (class "Default")
      (node (ref "IC3") (pin "40") (pinfunction "PL5(OC5C)_40") (pintype "bidirectional"))
      (node (ref "XIOL") (pin "10") (pinfunction "10_10") (pintype "passive"))
    )
    (net (code "73") (name "/PL6") (class "Default")
      (node (ref "IC3") (pin "41") (pinfunction "PL6_41") (pintype "bidirectional"))
      (node (ref "XIOL") (pin "11") (pinfunction "11_11") (pintype "passive"))
    )
    (net (code "74") (name "/PL7") (class "Default")
      (node (ref "IC3") (pin "42") (pinfunction "PL7_42") (pintype "bidirectional"))
      (node (ref "XIOL") (pin "12") (pinfunction "12_12") (pintype "passive"))
    )
    (net (code "75") (name "/PWRIN") (class "Default")
      (node (ref "D1") (pin "A") (pinfunction "A_A") (pintype "passive"))
      (node (ref "X1") (pin "2") (pinfunction "2_2") (pintype "power_in"))
    )
    (net (code "76") (name "/RD+") (class "Default")
      (node (ref "IC4") (pin "29") (pinfunction "D+_29") (pintype "bidirectional"))
      (node (ref "RN2") (pin "4") (pinfunction "1_4") (pintype "passive"))
    )
    (net (code "77") (name "/RD-") (class "Default")
      (node (ref "IC4") (pin "30") (pinfunction "D-_30") (pintype "bidirectional"))
      (node (ref "RN2") (pin "1") (pinfunction "1_1") (pintype "passive"))
    )
    (net (code "78") (name "/RESET") (class "Default")
      (node (ref "C1") (pin "1") (pinfunction "1_1") (pintype "passive"))
      (node (ref "C7") (pin "2") (pinfunction "2_2") (pintype "passive"))
      (node (ref "IC3") (pin "30") (pinfunction "RESET_30") (pintype "input"))
      (node (ref "ICSP") (pin "5") (pinfunction "5_5") (pintype "passive"))
      (node (ref "POWER") (pin "1") (pinfunction "1_1") (pintype "passive"))
      (node (ref "RESET") (pin "3") (pinfunction "3_3") (pintype "passive"))
      (node (ref "RESET") (pin "4") (pinfunction "4_4") (pintype "passive"))
      (node (ref "RESET-EN") (pin "1") (pinfunction "1_1") (pintype "passive"))
      (node (ref "RESET-EN") (pin "2") (pinfunction "2_2") (pintype "passive"))
      (node (ref "RN1") (pin "1") (pinfunction "1_1") (pintype "passive"))
    )
    (net (code "79") (name "/RESET2") (class "Default")
      (node (ref "IC4") (pin "24") (pinfunction "RESET(PC1/DW)_24") (pintype "input"))
      (node (ref "ICSP1") (pin "5") (pinfunction "5_5") (pintype "passive"))
      (node (ref "RN5") (pin "8") (pinfunction "2_8") (pintype "passive"))
    )
    (net (code "80") (name "/RXD1") (class "Default")
      (node (ref "COMMUNICATION") (pin "3") (pinfunction "3_3") (pintype "passive"))
      (node (ref "IC3") (pin "45") (pinfunction "(RXD1/INT2)PD2_45") (pintype "bidirectional"))
    )
    (net (code "81") (name "/RXD2") (class "Default")
      (node (ref "COMMUNICATION") (pin "5") (pinfunction "5_5") (pintype "passive"))
      (node (ref "IC3") (pin "12") (pinfunction "PH0(RXD2)_12") (pintype "bidirectional"))
    )
    (net (code "82") (name "/RXD3") (class "Default")
      (node (ref "COMMUNICATION") (pin "7") (pinfunction "7_7") (pintype "passive"))
      (node (ref "IC3") (pin "63") (pinfunction "PJ0(RXD3/PCINT9)_63") (pintype "bidirectional"))
    )
    (net (code "83") (name "/RXL") (class "Default")
      (node (ref "IC4") (pin "10") (pinfunction "(INT5/AIN3)PD4_10") (pintype "bidirectional"))
      (node (ref "RX") (pin "C") (pinfunction "C_C") (pintype "passive"))
    )
    (net (code "84") (name "/SCK2") (class "Default")
      (node (ref "IC4") (pin "15") (pinfunction "(SCLK/PCINT1)PB1_15") (pintype "bidirectional"))
      (node (ref "ICSP1") (pin "3") (pinfunction "3_3") (pintype "passive"))
    )
    (net (code "85") (name "/SCL") (class "Default")
      (node (ref "COMMUNICATION") (pin "1") (pinfunction "1_1") (pintype "passive"))
      (node (ref "IC3") (pin "43") (pinfunction "(SCL/INT0)PD0_43") (pintype "bidirectional"))
      (node (ref "RN1") (pin "2") (pinfunction "1_2") (pintype "passive"))
    )
    (net (code "86") (name "/SDA") (class "Default")
      (node (ref "COMMUNICATION") (pin "2") (pinfunction "2_2") (pintype "passive"))
      (node (ref "IC3") (pin "44") (pinfunction "(SDA/INT1)PD1_44") (pintype "bidirectional"))
      (node (ref "RN1") (pin "3") (pinfunction "1_3") (pintype "passive"))
    )
    (net (code "87") (name "/TXD1") (class "Default")
      (node (ref "COMMUNICATION") (pin "4") (pinfunction "4_4") (pintype "passive"))
      (node (ref "IC3") (pin "46") (pinfunction "(TXD1/INT3)PD3_46") (pintype "bidirectional"))
    )
    (net (code "88") (name "/TXD2") (class "Default")
      (node (ref "COMMUNICATION") (pin "6") (pinfunction "6_6") (pintype "passive"))
      (node (ref "IC3") (pin "13") (pinfunction "PH1(TXD2)_13") (pintype "bidirectional"))
    )
    (net (code "89") (name "/TXD3") (class "Default")
      (node (ref "COMMUNICATION") (pin "8") (pinfunction "8_8") (pintype "passive"))
      (node (ref "IC3") (pin "64") (pinfunction "PJ1(TXD3/PCINT10)_64") (pintype "bidirectional"))
    )
    (net (code "90") (name "/TXL") (class "Default")
      (node (ref "IC4") (pin "11") (pinfunction "(XCK/AIN4/PCINT12)PD5_11") (pintype "bidirectional"))
      (node (ref "TX") (pin "C") (pinfunction "C_C") (pintype "passive"))
    )
    (net (code "91") (name "/UGND") (class "Default")
      (node (ref "C10") (pin "2") (pinfunction "2_2") (pintype "passive"))
      (node (ref "GROUND") (pin "1") (pinfunction "1_1") (pintype "passive"))
      (node (ref "IC4") (pin "28") (pinfunction "UGND_28") (pintype "power_in"))
      (node (ref "L1") (pin "1") (pinfunction "1_1") (pintype "passive"))
      (node (ref "X2") (pin "4") (pinfunction "4_4") (pintype "bidirectional"))
    )
    (net (code "92") (name "/USBVCC") (class "Default")
      (node (ref "C8") (pin "1") (pinfunction "1_1") (pintype "passive"))
      (node (ref "F1") (pin "1") (pinfunction "1_1") (pintype "passive"))
      (node (ref "IC4") (pin "31") (pinfunction "UVCC_31") (pintype "power_in"))
      (node (ref "T2") (pin "1") (pinfunction "D_1") (pintype "passive"))
    )
    (net (code "93") (name "/USHIELD") (class "Default")
      (node (ref "L1") (pin "2") (pinfunction "2_2") (pintype "passive"))
      (node (ref "X2") (pin "P$1") (pinfunction "P$1_P$1") (pintype "bidirectional"))
      (node (ref "X2") (pin "P$2") (pinfunction "P$2_P$2") (pintype "bidirectional"))
      (node (ref "Z1") (pin "1") (pinfunction "1_1") (pintype "passive"))
      (node (ref "Z2") (pin "1") (pinfunction "1_1") (pintype "passive"))
    )
    (net (code "94") (name "/VIN") (class "Default")
      (node (ref "C2") (pin "1") (pinfunction "1_1") (pintype "passive"))
      (node (ref "D1") (pin "C") (pinfunction "C_C") (pintype "passive"))
      (node (ref "IC1") (pin "3") (pinfunction "IN_3") (pintype "input"))
      (node (ref "IC2") (pin "3") (pinfunction "VI_3") (pintype "input"))
      (node (ref "PC1") (pin "+") (pinfunction "+_+") (pintype "passive"))
      (node (ref "POWER") (pin "6") (pinfunction "6_6") (pintype "passive"))
      (node (ref "RN5") (pin "6") (pinfunction "2_6") (pintype "passive"))
    )
    (net (code "95") (name "/VUCAP") (class "Default")
      (node (ref "C10") (pin "1") (pinfunction "1_1") (pintype "passive"))
      (node (ref "IC4") (pin "27") (pinfunction "UCAP_27") (pintype "passive"))
    )
    (net (code "96") (name "/XT1") (class "Default")
      (node (ref "C16") (pin "1") (pinfunction "1_1") (pintype "passive"))
      (node (ref "Q1") (pin "2") (pinfunction "2_2") (pintype "passive"))
      (node (ref "R2") (pin "1") (pinfunction "1_1") (pintype "passive"))
      (node (ref "R4") (pin "2") (pinfunction "2_2") (pintype "passive"))
      (node (ref "Y2") (pin "3") (pinfunction "3_3") (pintype "passive"))
    )
    (net (code "97") (name "/XT1R") (class "Default")
      (node (ref "IC4") (pin "1") (pinfunction "XTAL1_1") (pintype "bidirectional"))
      (node (ref "R4") (pin "1") (pinfunction "1_1") (pintype "passive"))
    )
    (net (code "98") (name "/XT2") (class "Default")
      (node (ref "C17") (pin "1") (pinfunction "1_1") (pintype "passive"))
      (node (ref "IC4") (pin "2") (pinfunction "XTAL2(PC0)_2") (pintype "bidirectional"))
      (node (ref "Q1") (pin "1") (pinfunction "1_1") (pintype "passive"))
      (node (ref "R2") (pin "2") (pinfunction "2_2") (pintype "passive"))
      (node (ref "Y2") (pin "1") (pinfunction "1_1") (pintype "passive"))
    )
    (net (code "99") (name "/XTAL1") (class "Default")
      (node (ref "C14") (pin "2") (pinfunction "2_2") (pintype "passive"))
      (node (ref "Q2") (pin "2") (pinfunction "2_2") (pintype "passive"))
      (node (ref "R1") (pin "1") (pinfunction "1_1") (pintype "passive"))
      (node (ref "R3") (pin "2") (pinfunction "2_2") (pintype "passive"))
      (node (ref "Y1") (pin "3") (pinfunction "3_3") (pintype "passive"))
    )
    (net (code "100") (name "/XTAL1R") (class "Default")
      (node (ref "IC3") (pin "34") (pinfunction "XTAL1_34") (pintype "input"))
      (node (ref "R3") (pin "1") (pinfunction "1_1") (pintype "passive"))
    )
    (net (code "101") (name "/XTAL2") (class "Default")
      (node (ref "C15") (pin "2") (pinfunction "2_2") (pintype "passive"))
      (node (ref "IC3") (pin "33") (pinfunction "XTAL2_33") (pintype "output"))
      (node (ref "Q2") (pin "1") (pinfunction "1_1") (pintype "passive"))
      (node (ref "R1") (pin "2") (pinfunction "2_2") (pintype "passive"))
      (node (ref "Y1") (pin "1") (pinfunction "1_1") (pintype "passive"))
    )
    (net (code "102") (name "/XVCC") (class "Default")
      (node (ref "F1") (pin "2") (pinfunction "2_2") (pintype "passive"))
      (node (ref "X2") (pin "1") (pinfunction "1_1") (pintype "bidirectional"))
    )
    (net (code "103") (name "GND") (class "Default")
      (node (ref "C1") (pin "2") (pinfunction "2_2") (pintype "passive"))
      (node (ref "C11") (pin "1") (pinfunction "1_1") (pintype "passive"))
      (node (ref "C12") (pin "1") (pinfunction "1_1") (pintype "passive"))
      (node (ref "C13") (pin "1") (pinfunction "1_1") (pintype "passive"))
      (node (ref "C14") (pin "1") (pinfunction "1_1") (pintype "passive"))
      (node (ref "C15") (pin "1") (pinfunction "1_1") (pintype "passive"))
      (node (ref "C16") (pin "2") (pinfunction "2_2") (pintype "passive"))
      (node (ref "C17") (pin "2") (pinfunction "2_2") (pintype "passive"))
      (node (ref "C2") (pin "2") (pinfunction "2_2") (pintype "passive"))
      (node (ref "C3") (pin "2") (pinfunction "2_2") (pintype "passive"))
      (node (ref "C4") (pin "2") (pinfunction "2_2") (pintype "passive"))
      (node (ref "C5") (pin "2") (pinfunction "2_2") (pintype "passive"))
      (node (ref "C6") (pin "2") (pinfunction "2_2") (pintype "passive"))
      (node (ref "C8") (pin "2") (pinfunction "2_2") (pintype "passive"))
      (node (ref "C9") (pin "2") (pinfunction "2_2") (pintype "passive"))
      (node (ref "GROUND") (pin "2") (pinfunction "2_2") (pintype "passive"))
      (node (ref "IC1") (pin "1") (pinfunction "GND/ADJ_1") (pintype "input"))
      (node (ref "IC2") (pin "1") (pinfunction "ADJ_1") (pintype "input"))
      (node (ref "IC3") (pin "11") (pinfunction "GND_11") (pintype "power_in"))
      (node (ref "IC3") (pin "32") (pinfunction "GND1_32") (pintype "power_in"))
      (node (ref "IC3") (pin "62") (pinfunction "GND2_62") (pintype "power_in"))
      (node (ref "IC3") (pin "81") (pinfunction "GND3_81") (pintype "power_in"))
      (node (ref "IC3") (pin "99") (pinfunction "AGND_99") (pintype "power_in"))
      (node (ref "IC4") (pin "3") (pinfunction "GND_3") (pintype "power_in"))
      (node (ref "IC4") (pin "EXP") (pinfunction "PAD_EXP") (pintype "power_in"))
      (node (ref "IC5") (pin "2") (pinfunction "-IN_2") (pintype "input"))
      (node (ref "IC5") (pin "3") (pinfunction "+IN_3") (pintype "input"))
      (node (ref "IC5") (pin "4") (pinfunction "V-_4") (pintype "power_in"))
      (node (ref "IC6") (pin "2") (pinfunction "GND_2") (pintype "power_in"))
      (node (ref "ICSP") (pin "6") (pinfunction "6_6") (pintype "passive"))
      (node (ref "ICSP1") (pin "6") (pinfunction "6_6") (pintype "passive"))
      (node (ref "JP3") (pin "1") (pinfunction "1_1") (pintype "passive"))
      (node (ref "JP4") (pin "1") (pinfunction "1_1") (pintype "passive"))
      (node (ref "L") (pin "C") (pinfunction "C_C") (pintype "passive"))
      (node (ref "PC1") (pin "-") (pinfunction "-_-") (pintype "passive"))
      (node (ref "PC2") (pin "-") (pinfunction "-_-") (pintype "passive"))
      (node (ref "POWER") (pin "4") (pinfunction "4_4") (pintype "passive"))
      (node (ref "POWER") (pin "5") (pinfunction "5_5") (pintype "passive"))
      (node (ref "PWMH") (pin "7") (pinfunction "7_7") (pintype "passive"))
      (node (ref "RESET") (pin "1") (pinfunction "1_1") (pintype "passive"))
      (node (ref "RESET") (pin "2") (pinfunction "2_2") (pintype "passive"))
      (node (ref "RN5") (pin "2") (pinfunction "1_2") (pintype "passive"))
      (node (ref "UBOOT") (pin "2") (pinfunction "2_2") (pintype "passive"))
      (node (ref "X1") (pin "1") (pinfunction "1_1") (pintype "power_in"))
      (node (ref "X1") (pin "3") (pinfunction "3_3") (pintype "power_in"))
      (node (ref "Y1") (pin "2") (pinfunction "2_2") (pintype "passive"))
      (node (ref "Y2") (pin "2") (pinfunction "2_2") (pintype "passive"))
    )
    (net (code "104") (name "Net-(RN3D-1)") (class "Default")
      (node (ref "L") (pin "A") (pinfunction "A_A") (pintype "passive"))
      (node (ref "RN3") (pin "4") (pinfunction "1_4") (pintype "passive"))
    )
    (net (code "105") (name "Net-(RN4C-1)") (class "Default")
      (node (ref "RN4") (pin "3") (pinfunction "1_3") (pintype "passive"))
      (node (ref "TX") (pin "A") (pinfunction "A_A") (pintype "passive"))
    )
    (net (code "106") (name "Net-(RN4D-1)") (class "Default")
      (node (ref "RN4") (pin "4") (pinfunction "1_4") (pintype "passive"))
      (node (ref "RX") (pin "A") (pinfunction "A_A") (pintype "passive"))
    )
    (net (code "107") (name "unconnected-(D2-PadA)") (class "Default")
      (node (ref "D2") (pin "A") (pinfunction "A_A") (pintype "passive"))
    )
    (net (code "108") (name "unconnected-(D2-PadK)") (class "Default")
      (node (ref "D2") (pin "K") (pinfunction "K_K") (pintype "passive"))
    )
    (net (code "109") (name "unconnected-(IC3-(CLKO{slash}ICP3{slash}INT7)PE7-Pad9)") (class "Default")
      (node (ref "IC3") (pin "9") (pinfunction "(CLKO/ICP3/INT7)PE7_9") (pintype "bidirectional"))
    )
    (net (code "110") (name "unconnected-(IC3-(ICP1)PD4-Pad47)") (class "Default")
      (node (ref "IC3") (pin "47") (pinfunction "(ICP1)PD4_47") (pintype "bidirectional"))
    )
    (net (code "111") (name "unconnected-(IC3-(OC1A{slash}PCINT5)PB5-Pad24)") (class "Default")
      (node (ref "IC3") (pin "24") (pinfunction "(OC1A/PCINT5)PB5_24") (pintype "bidirectional"))
    )
    (net (code "112") (name "unconnected-(IC3-(T1)PD6-Pad49)") (class "Default")
      (node (ref "IC3") (pin "49") (pinfunction "(T1)PD6_49") (pintype "bidirectional"))
    )
    (net (code "113") (name "unconnected-(IC3-(T3{slash}INT6)PE6-Pad8)") (class "Default")
      (node (ref "IC3") (pin "8") (pinfunction "(T3/INT6)PE6_8") (pintype "bidirectional"))
    )
    (net (code "114") (name "unconnected-(IC3-(TOSC1)PG4-Pad29)") (class "Default")
      (node (ref "IC3") (pin "29") (pinfunction "(TOSC1)PG4_29") (pintype "bidirectional"))
    )
    (net (code "115") (name "unconnected-(IC3-(TOSC2)PG3-Pad28)") (class "Default")
      (node (ref "IC3") (pin "28") (pinfunction "(TOSC2)PG3_28") (pintype "bidirectional"))
    )
    (net (code "116") (name "unconnected-(IC3-(XCK0{slash}AIN0)PE2-Pad4)") (class "Default")
      (node (ref "IC3") (pin "4") (pinfunction "(XCK0/AIN0)PE2_4") (pintype "bidirectional"))
    )
    (net (code "117") (name "unconnected-(IC3-(XCK1)PD5-Pad48)") (class "Default")
      (node (ref "IC3") (pin "48") (pinfunction "(XCK1)PD5_48") (pintype "bidirectional"))
    )
    (net (code "118") (name "unconnected-(IC3-PH2(XCK2)-Pad14)") (class "Default")
      (node (ref "IC3") (pin "14") (pinfunction "PH2(XCK2)_14") (pintype "bidirectional"))
    )
    (net (code "119") (name "unconnected-(IC3-PH7(T4)-Pad27)") (class "Default")
      (node (ref "IC3") (pin "27") (pinfunction "PH7(T4)_27") (pintype "bidirectional"))
    )
    (net (code "120") (name "unconnected-(IC3-PJ2(XCK3{slash}PCINT11)-Pad65)") (class "Default")
      (node (ref "IC3") (pin "65") (pinfunction "PJ2(XCK3/PCINT11)_65") (pintype "bidirectional"))
    )
    (net (code "121") (name "unconnected-(IC3-PJ3(PCINT12)-Pad66)") (class "Default")
      (node (ref "IC3") (pin "66") (pinfunction "PJ3(PCINT12)_66") (pintype "bidirectional"))
    )
    (net (code "122") (name "unconnected-(IC3-PJ4(PCINT13)-Pad67)") (class "Default")
      (node (ref "IC3") (pin "67") (pinfunction "PJ4(PCINT13)_67") (pintype "bidirectional"))
    )
    (net (code "123") (name "unconnected-(IC3-PJ5(PCINT14)-Pad68)") (class "Default")
      (node (ref "IC3") (pin "68") (pinfunction "PJ5(PCINT14)_68") (pintype "bidirectional"))
    )
    (net (code "124") (name "unconnected-(IC3-PJ6(PCINT15)-Pad69)") (class "Default")
      (node (ref "IC3") (pin "69") (pinfunction "PJ6(PCINT15)_69") (pintype "bidirectional"))
    )
    (net (code "125") (name "unconnected-(IC3-PJ7-Pad79)") (class "Default")
      (node (ref "IC3") (pin "79") (pinfunction "PJ7_79") (pintype "bidirectional"))
    )
    (net (code "126") (name "unconnected-(IC4-(AIN0{slash}INT1)PD1-Pad7)") (class "Default")
      (node (ref "IC4") (pin "7") (pinfunction "(AIN0/INT1)PD1_7") (pintype "bidirectional"))
    )
    (net (code "127") (name "unconnected-(IC4-(AIN2{slash}PCINT11)PC2-Pad5)") (class "Default")
      (node (ref "IC4") (pin "5") (pinfunction "(AIN2/PCINT11)PC2_5") (pintype "bidirectional"))
    )
    (net (code "128") (name "unconnected-(IC4-(INT4{slash}ICP1{slash}CLK0)PC7-Pad22)") (class "Default")
      (node (ref "IC4") (pin "22") (pinfunction "(INT4/ICP1/CLK0)PC7_22") (pintype "bidirectional"))
    )
    (net (code "129") (name "unconnected-(IC4-(OC0B{slash}INT0)PD0-Pad6)") (class "Default")
      (node (ref "IC4") (pin "6") (pinfunction "(OC0B/INT0)PD0_6") (pintype "bidirectional"))
    )
    (net (code "130") (name "unconnected-(IC4-(OC1A{slash}PCINT8)PC6-Pad23)") (class "Default")
      (node (ref "IC4") (pin "23") (pinfunction "(OC1A/PCINT8)PC6_23") (pintype "bidirectional"))
    )
    (net (code "131") (name "unconnected-(IC4-(PCINT5)PB5-Pad19)") (class "Default")
      (node (ref "IC4") (pin "19") (pinfunction "(PCINT5)PB5_19") (pintype "bidirectional"))
    )
    (net (code "132") (name "unconnected-(IC4-(PCINT6)PB6-Pad20)") (class "Default")
      (node (ref "IC4") (pin "20") (pinfunction "(PCINT6)PB6_20") (pintype "bidirectional"))
    )
    (net (code "133") (name "unconnected-(IC4-(PCINT7{slash}OC0A{slash}OC1C)PB7-Pad21)") (class "Default")
      (node (ref "IC4") (pin "21") (pinfunction "(PCINT7/OC0A/OC1C)PB7_21") (pintype "bidirectional"))
    )
    (net (code "134") (name "unconnected-(IC4-(PCINT9{slash}OC1B)PC5-Pad25)") (class "Default")
      (node (ref "IC4") (pin "25") (pinfunction "(PCINT9/OC1B)PC5_25") (pintype "bidirectional"))
    )
    (net (code "135") (name "unconnected-(IC4-(PCINT10)PC4-Pad26)") (class "Default")
      (node (ref "IC4") (pin "26") (pinfunction "(PCINT10)PC4_26") (pintype "bidirectional"))
    )
    (net (code "136") (name "unconnected-(IC4-(RTS{slash}AIN5{slash}INT6)PD6-Pad12)") (class "Default")
      (node (ref "IC4") (pin "12") (pinfunction "(RTS/AIN5/INT6)PD6_12") (pintype "bidirectional"))
    )
    (net (code "137") (name "unconnected-(IC4-(SS{slash}PCINT0)PB0-Pad14)") (class "Default")
      (node (ref "IC4") (pin "14") (pinfunction "(SS/PCINT0)PB0_14") (pintype "bidirectional"))
    )
    (net (code "138") (name "unconnected-(IC4-(T1{slash}PCINT4)PB4-Pad18)") (class "Default")
      (node (ref "IC4") (pin "18") (pinfunction "(T1/PCINT4)PB4_18") (pintype "bidirectional"))
    )
    (net (code "139") (name "unconnected-(IC5A-OUT-Pad1)") (class "Default")
      (node (ref "IC5") (pin "1") (pinfunction "OUT_1") (pintype "output"))
    )
    (net (code "140") (name "unconnected-(IC6-NC{slash}FB-Pad4)") (class "Default")
      (node (ref "IC6") (pin "4") (pinfunction "NC/FB_4") (pintype "passive"))
    )
    (net (code "141") (name "unconnected-(PWMH-Pad4)") (class "Default")
      (node (ref "PWMH") (pin "4") (pinfunction "4_4") (pintype "passive"))
    )
    (net (code "142") (name "unconnected-(RN1D-1-Pad4)") (class "Default")
      (node (ref "RN1") (pin "4") (pinfunction "1_4") (pintype "passive"))
    )
    (net (code "143") (name "unconnected-(RN1D-2-Pad5)") (class "Default")
      (node (ref "RN1") (pin "5") (pinfunction "2_5") (pintype "passive"))
    )
    (net (code "144") (name "unconnected-(RN2B-1-Pad2)") (class "Default")
      (node (ref "RN2") (pin "2") (pinfunction "1_2") (pintype "passive"))
    )
    (net (code "145") (name "unconnected-(RN2B-2-Pad7)") (class "Default")
      (node (ref "RN2") (pin "7") (pinfunction "2_7") (pintype "passive"))
    )
    (net (code "146") (name "unconnected-(RN2C-1-Pad3)") (class "Default")
      (node (ref "RN2") (pin "3") (pinfunction "1_3") (pintype "passive"))
    )
    (net (code "147") (name "unconnected-(RN2C-2-Pad6)") (class "Default")
      (node (ref "RN2") (pin "6") (pinfunction "2_6") (pintype "passive"))
    )
    (net (code "148") (name "unconnected-(RN3-Pad1)") (class "Default")
      (node (ref "RN3") (pin "1") (pinfunction "1_1") (pintype "passive"))
    )
    (net (code "149") (name "unconnected-(RN3A-2-Pad8)") (class "Default")
      (node (ref "RN3") (pin "8") (pinfunction "2_8") (pintype "passive"))
    )
    (net (code "150") (name "unconnected-(RN3B-1-Pad2)") (class "Default")
      (node (ref "RN3") (pin "2") (pinfunction "1_2") (pintype "passive"))
    )
    (net (code "151") (name "unconnected-(RN3B-2-Pad7)") (class "Default")
      (node (ref "RN3") (pin "7") (pinfunction "2_7") (pintype "passive"))
    )
    (net (code "152") (name "unconnected-(RN3C-2-Pad6)") (class "Default")
      (node (ref "RN3") (pin "6") (pinfunction "2_6") (pintype "passive"))
    )
    (net (code "153") (name "unconnected-(RN5D-1-Pad4)") (class "Default")
      (node (ref "RN5") (pin "4") (pinfunction "1_4") (pintype "passive"))
    )
    (net (code "154") (name "unconnected-(RN5D-2-Pad5)") (class "Default")
      (node (ref "RN5") (pin "5") (pinfunction "2_5") (pintype "passive"))
    )
  )
)
